# RKJXM1_Breakout_Output_Pins_v14.net
KiCad netlist of a schematic drawn in EAGLE
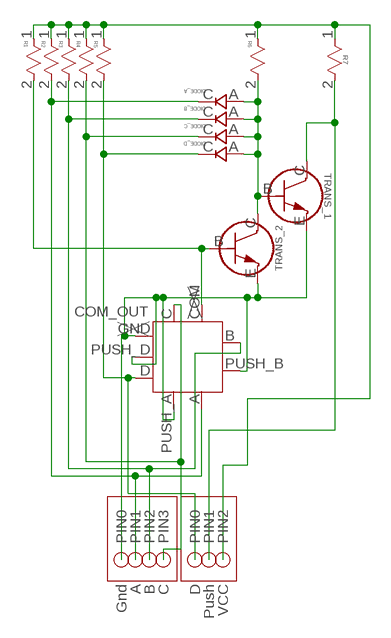
[diagram p0: schematic, sheet 1]

(export (version "E")
  (design (tool "Eeschema 10.0.6"))
  (components
    (comp (ref "DIODE_A")
      (value "DIODE_SCHOTTKY_SMD_USC_TOS")
      (footprint "eagle-import:DIODE_SCHOTTKY_SMD_USC_TOS")
      (libsource (lib "eagle-import") (part "DIODE_SCHOTTKY_SMD_USC_TOS"))
    )
    (comp (ref "DIODE_B")
      (value "DIODE_SCHOTTKY_SMD_USC_TOS")
      (footprint "eagle-import:DIODE_SCHOTTKY_SMD_USC_TOS")
      (libsource (lib "eagle-import") (part "DIODE_SCHOTTKY_SMD_USC_TOS"))
    )
    (comp (ref "DIODE_C")
      (value "DIODE_SCHOTTKY_SMD_USC_TOS")
      (footprint "eagle-import:DIODE_SCHOTTKY_SMD_USC_TOS")
      (libsource (lib "eagle-import") (part "DIODE_SCHOTTKY_SMD_USC_TOS"))
    )
    (comp (ref "DIODE_D")
      (value "DIODE_SCHOTTKY_SMD_USC_TOS")
      (footprint "eagle-import:DIODE_SCHOTTKY_SMD_USC_TOS")
      (libsource (lib "eagle-import") (part "DIODE_SCHOTTKY_SMD_USC_TOS"))
    )
    (comp (ref "R1")
      (value "RESISTOR_1K_SMD_RNCP0805FTD1K00STA_RNCP0805_STP-L")
      (footprint "eagle-import:STA_RNCP0805_STP-L")
      (fields (field (name "MANUFACTURER_PART_NUMBER") "RNCP0805FTD1K00"))
      (libsource (lib "eagle-import") (part "RESISTOR_1K_SMD_RNCP0805FTD1K00STA_RNCP0805_STP-L"))
    )
    (comp (ref "R2")
      (value "RESISTOR_1K_SMD_RNCP0805FTD1K00STA_RNCP0805_STP-L")
      (footprint "eagle-import:STA_RNCP0805_STP-L")
      (fields (field (name "MANUFACTURER_PART_NUMBER") "RNCP0805FTD1K00"))
      (libsource (lib "eagle-import") (part "RESISTOR_1K_SMD_RNCP0805FTD1K00STA_RNCP0805_STP-L"))
    )
    (comp (ref "R3")
      (value "RESISTOR_1K_SMD_RNCP0805FTD1K00STA_RNCP0805_STP-L")
      (footprint "eagle-import:STA_RNCP0805_STP-L")
      (fields (field (name "MANUFACTURER_PART_NUMBER") "RNCP0805FTD1K00"))
      (libsource (lib "eagle-import") (part "RESISTOR_1K_SMD_RNCP0805FTD1K00STA_RNCP0805_STP-L"))
    )
    (comp (ref "R4")
      (value "RESISTOR_1K_SMD_RNCP0805FTD1K00STA_RNCP0805_STP-L")
      (footprint "eagle-import:STA_RNCP0805_STP-L")
      (fields (field (name "MANUFACTURER_PART_NUMBER") "RNCP0805FTD1K00"))
      (libsource (lib "eagle-import") (part "RESISTOR_1K_SMD_RNCP0805FTD1K00STA_RNCP0805_STP-L"))
    )
    (comp (ref "R5")
      (value "RESISTOR_1K_SMD_RNCP0805FTD1K00STA_RNCP0805_STP-L")
      (footprint "eagle-import:STA_RNCP0805_STP-L")
      (fields (field (name "MANUFACTURER_PART_NUMBER") "RNCP0805FTD1K00"))
      (libsource (lib "eagle-import") (part "RESISTOR_1K_SMD_RNCP0805FTD1K00STA_RNCP0805_STP-L"))
    )
    (comp (ref "R6")
      (value "RESISTOR_1K_SMD_RNCP0805FTD1K00STA_RNCP0805_STP-L")
      (footprint "eagle-import:STA_RNCP0805_STP-L")
      (fields (field (name "MANUFACTURER_PART_NUMBER") "RNCP0805FTD1K00"))
      (libsource (lib "eagle-import") (part "RESISTOR_1K_SMD_RNCP0805FTD1K00STA_RNCP0805_STP-L"))
    )
    (comp (ref "R7")
      (value "RESISTOR_1K_SMD_RNCP0805FTD1K00STA_RNCP0805_STP-L")
      (footprint "eagle-import:STA_RNCP0805_STP-L")
      (fields (field (name "MANUFACTURER_PART_NUMBER") "RNCP0805FTD1K00"))
      (libsource (lib "eagle-import") (part "RESISTOR_1K_SMD_RNCP0805FTD1K00STA_RNCP0805_STP-L"))
    )
    (comp (ref "RKJXM1_SWITCH")
      (value "RKJXM1_V3")
      (footprint "eagle-import:RKJXM1_FOOT_V3")
      (fields (field (name "PART_NAME") "RKJXM1_Switch"))
      (libsource (lib "eagle-import") (part "RKJXM1_V3"))
    )
    (comp (ref "TRANS_1")
      (value "TRANS_NPN_SMD_MMBT3904-TPSOT-23_MCC-L")
      (footprint "eagle-import:SOT-23_MCC-L")
      (fields
        (field (name "MANUFACTURER_PART_NUMBER") "MMBT3904-TP")
        (field (name "COPYRIGHT") "Copyright (C) 2018 Accelerated Designs. All rights reserved")
      )
      (libsource (lib "eagle-import") (part "TRANS_NPN_SMD_MMBT3904-TPSOT-23_MCC-L"))
    )
    (comp (ref "TRANS_2")
      (value "TRANS_NPN_SMD_MMBT3904-TPSOT-23_MCC-L")
      (footprint "eagle-import:SOT-23_MCC-L")
      (fields
        (field (name "MANUFACTURER_PART_NUMBER") "MMBT3904-TP")
        (field (name "COPYRIGHT") "Copyright (C) 2018 Accelerated Designs. All rights reserved")
      )
      (libsource (lib "eagle-import") (part "TRANS_NPN_SMD_MMBT3904-TPSOT-23_MCC-L"))
    )
    (comp (ref "U$3")
      (value "JST_ZH_4PIN")
      (footprint "eagle-import:JST_ZH_4PIN")
      (fields
        (field (name "LABEL") "4-Pin")
        (field (name "PIN0") "Gnd")
        (field (name "PIN1") "A")
        (field (name "PIN2") "B")
        (field (name "PIN3") "C")
      )
      (libsource (lib "eagle-import") (part "JST_ZH_4PIN"))
    )
    (comp (ref "U$4")
      (value "JST_ZH_3PIN_NO_GND")
      (footprint "eagle-import:JST_ZH_3PIN_NO_GND")
      (fields
        (field (name "LABEL") "3-Pin")
        (field (name "PIN0") "D")
        (field (name "PIN1") "Push")
        (field (name "PIN2") "Vcc")
      )
      (libsource (lib "eagle-import") (part "JST_ZH_3PIN_NO_GND"))
    )
  )
  (nets
    (net (code "1") (name "Net-(DIODE_A-PadA)") (class "Default")
      (node (ref "DIODE_A") (pin "A") (pinfunction "A_A") (pintype "passive"))
      (node (ref "DIODE_B") (pin "A") (pinfunction "A_A") (pintype "passive"))
      (node (ref "DIODE_C") (pin "A") (pinfunction "A_A") (pintype "passive"))
      (node (ref "DIODE_D") (pin "A") (pinfunction "A_A") (pintype "passive"))
      (node (ref "R6") (pin "2") (pinfunction "2_2") (pintype "passive"))
      (node (ref "TRANS_1") (pin "B") (pinfunction "B_B") (pintype "passive"))
      (node (ref "TRANS_2") (pin "C") (pinfunction "C_C") (pintype "passive"))
    )
    (net (code "2") (name "Net-(DIODE_A-PadC)") (class "Default")
      (node (ref "DIODE_A") (pin "C") (pinfunction "C_C") (pintype "passive"))
      (node (ref "R2") (pin "2") (pinfunction "2_2") (pintype "passive"))
      (node (ref "RKJXM1_SWITCH") (pin "A") (pinfunction "A_A") (pintype "bidirectional"))
      (node (ref "U$3") (pin "PIN1") (pinfunction "PIN1_PIN1") (pintype "bidirectional"))
    )
    (net (code "3") (name "Net-(DIODE_B-PadC)") (class "Default")
      (node (ref "DIODE_B") (pin "C") (pinfunction "C_C") (pintype "passive"))
      (node (ref "R3") (pin "2") (pinfunction "2_2") (pintype "passive"))
      (node (ref "RKJXM1_SWITCH") (pin "B") (pinfunction "B_B") (pintype "bidirectional"))
      (node (ref "U$3") (pin "PIN2") (pinfunction "PIN2_PIN2") (pintype "bidirectional"))
    )
    (net (code "4") (name "Net-(DIODE_C-PadC)") (class "Default")
      (node (ref "DIODE_C") (pin "C") (pinfunction "C_C") (pintype "passive"))
      (node (ref "R4") (pin "2") (pinfunction "2_2") (pintype "passive"))
      (node (ref "RKJXM1_SWITCH") (pin "C") (pinfunction "C_C") (pintype "bidirectional"))
      (node (ref "U$3") (pin "PIN3") (pinfunction "PIN3_PIN3") (pintype "bidirectional"))
    )
    (net (code "5") (name "Net-(DIODE_D-PadC)") (class "Default")
      (node (ref "DIODE_D") (pin "C") (pinfunction "C_C") (pintype "passive"))
      (node (ref "R5") (pin "2") (pinfunction "2_2") (pintype "passive"))
      (node (ref "RKJXM1_SWITCH") (pin "D") (pinfunction "D_D") (pintype "bidirectional"))
      (node (ref "U$4") (pin "PIN0") (pinfunction "PIN0_PIN0") (pintype "bidirectional"))
    )
    (net (code "6") (name "Net-(R1-Pad1)") (class "Default")
      (node (ref "R1") (pin "1") (pinfunction "1_1") (pintype "passive"))
      (node (ref "R2") (pin "1") (pinfunction "1_1") (pintype "passive"))
      (node (ref "R3") (pin "1") (pinfunction "1_1") (pintype "passive"))
      (node (ref "R4") (pin "1") (pinfunction "1_1") (pintype "passive"))
      (node (ref "R5") (pin "1") (pinfunction "1_1") (pintype "passive"))
      (node (ref "R6") (pin "1") (pinfunction "1_1") (pintype "passive"))
      (node (ref "R7") (pin "1") (pinfunction "1_1") (pintype "passive"))
      (node (ref "U$4") (pin "PIN2") (pinfunction "PIN2_PIN2") (pintype "bidirectional"))
    )
    (net (code "7") (name "Net-(R1-Pad2)") (class "Default")
      (node (ref "R1") (pin "2") (pinfunction "2_2") (pintype "passive"))
      (node (ref "RKJXM1_SWITCH") (pin "COM") (pinfunction "COM_COM") (pintype "bidirectional"))
      (node (ref "TRANS_2") (pin "B") (pinfunction "B_B") (pintype "passive"))
    )
    (net (code "8") (name "Net-(R7-Pad2)") (class "Default")
      (node (ref "R7") (pin "2") (pinfunction "2_2") (pintype "passive"))
      (node (ref "TRANS_1") (pin "C") (pinfunction "C_C") (pintype "passive"))
      (node (ref "U$4") (pin "PIN1") (pinfunction "PIN1_PIN1") (pintype "bidirectional"))
    )
    (net (code "9") (name "Net-(RKJXM1_SWITCH-PadGND)") (class "Default")
      (node (ref "RKJXM1_SWITCH") (pin "GND") (pinfunction "GND_GND") (pintype "bidirectional"))
      (node (ref "RKJXM1_SWITCH") (pin "PUSH_A") (pinfunction "PUSH_A_PUSH_A") (pintype "bidirectional"))
      (node (ref "RKJXM1_SWITCH") (pin "PUSH_B") (pinfunction "PUSH_B_PUSH_B") (pintype "bidirectional"))
      (node (ref "RKJXM1_SWITCH") (pin "PUSH_D") (pinfunction "PUSH_D_PUSH_D") (pintype "bidirectional"))
      (node (ref "TRANS_1") (pin "E") (pinfunction "E_E") (pintype "passive"))
      (node (ref "TRANS_2") (pin "E") (pinfunction "E_E") (pintype "passive"))
      (node (ref "U$3") (pin "PIN0") (pinfunction "PIN0_PIN0") (pintype "bidirectional"))
    )
  )
)
